# Transconductance.net
KiCad netlist of a schematic drawn in Altium Designer
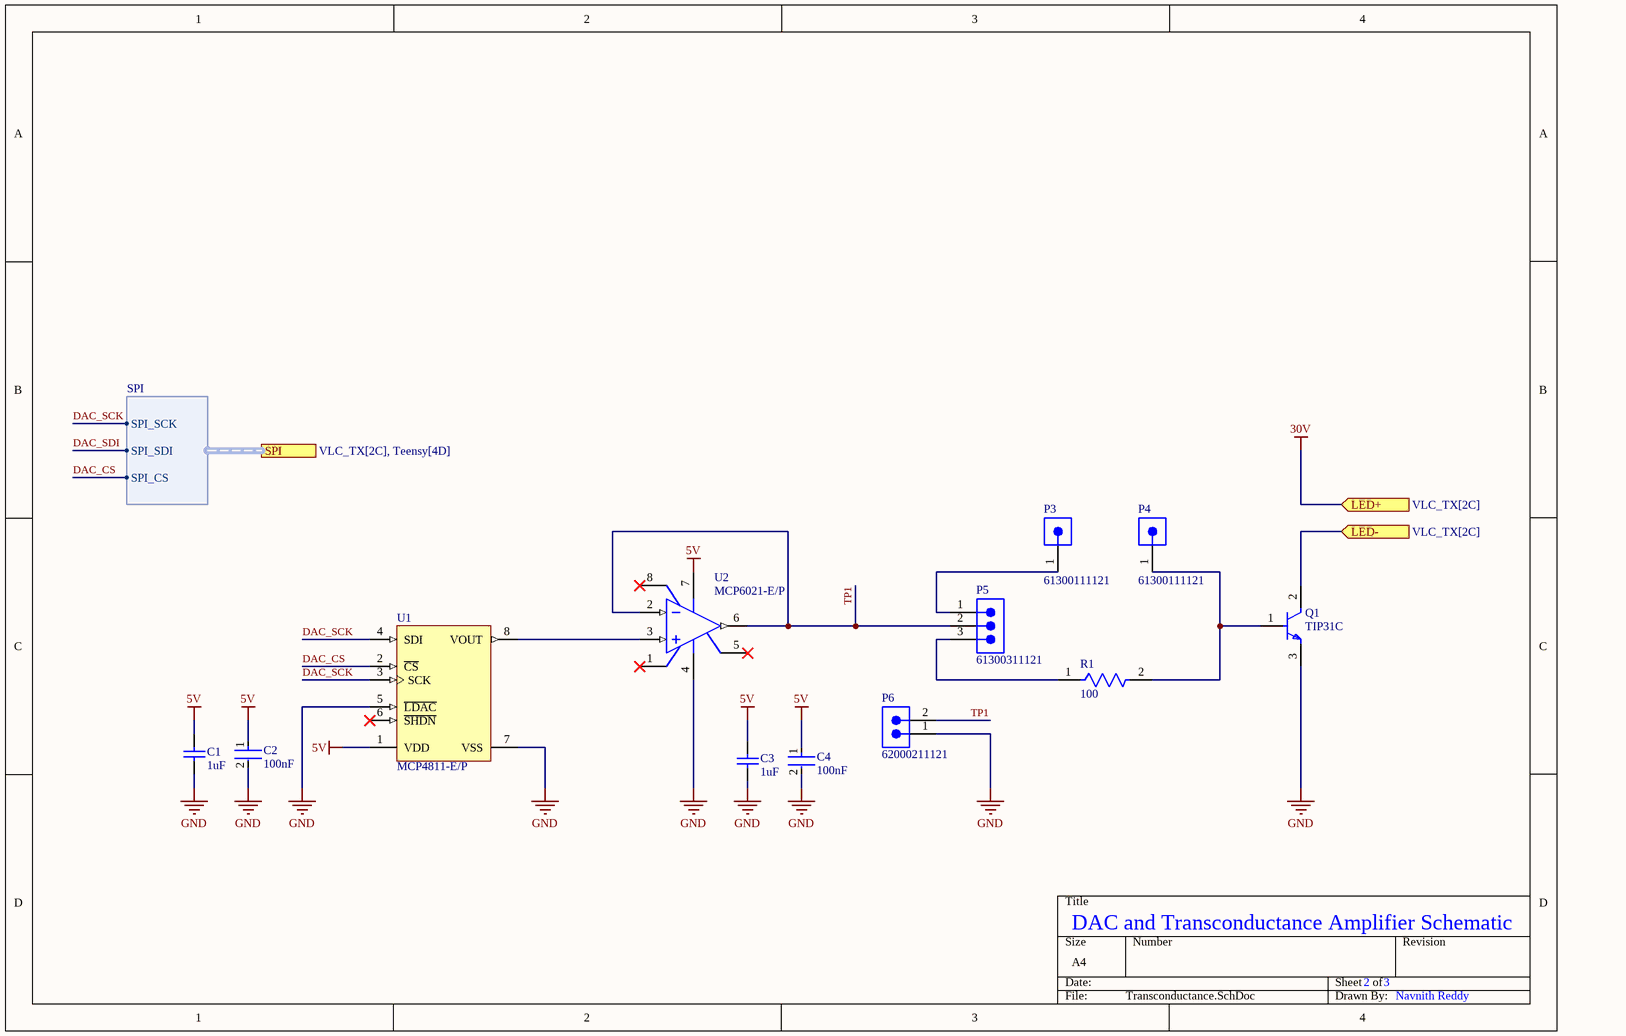
[diagram p0: Transconductance.SchDoc]

(export (version "E")
  (design (tool "Eeschema 10.0.6"))
  (components
    (comp (ref "C1")
      (value "1uF")
      (footprint "CAPC2013X145X50LL20T25")
      (fields (field (name "MANUFACTURER") "Kemet") (field (name "PART NUMBER") "C0805C105K4PACTU"))
      (libsource (lib "Altium Content Vault") (part "CAP"))
    )
    (comp (ref "C2")
      (value "100nF")
      (footprint "FP-C0805C-DN-MFG")
      (description "CAP CER 0.1UF 16V X7R 0805")
      (fields
        (field (name "OCTOPART") "https://octopart.com/c0805c104k4ractu-kemet-92155")
        (field (name "TOLERANCE") "0.1")
      )
      (libsource (lib "Altium Content Vault") (part "b4654b650e69147ec39a6b967a45e02"))
    )
    (comp (ref "C3")
      (value "1uF")
      (footprint "CAPC2013X145X50LL20T25")
      (fields (field (name "MANUFACTURER") "Kemet") (field (name "PART NUMBER") "C0805C105K4PACTU"))
      (libsource (lib "Altium Content Vault") (part "CAP"))
    )
    (comp (ref "C4")
      (value "100nF")
      (footprint "FP-C0805C-DN-MFG")
      (description "CAP CER 0.1UF 16V X7R 0805")
      (fields
        (field (name "OCTOPART") "https://octopart.com/c0805c104k4ractu-kemet-92155")
        (field (name "TOLERANCE") "0.1")
      )
      (libsource (lib "Altium Content Vault") (part "b4654b650e69147ec39a6b967a45e02"))
    )
    (comp (ref "P3")
      (value "61300111121")
      (footprint "61300111121")
      (libsource (lib "Altium Content Vault") (part "Header_Male_1R_01P"))
    )
    (comp (ref "P4")
      (value "61300111121")
      (footprint "61300111121")
      (libsource (lib "Altium Content Vault") (part "Header_Male_1R_01P"))
    )
    (comp (ref "P5")
      (value "61300311121")
      (footprint "61300311121")
      (libsource (lib "Altium Content Vault") (part "Header_Male_1R_03P"))
    )
    (comp (ref "P6")
      (value "62000211121")
      (footprint "62000211121")
      (libsource (lib "Altium Content Vault") (part "Header_Male_1R_02P"))
    )
    (comp (ref "Q1")
      (value "TIP31C")
      (footprint "FP-TO-220-P0A0015988-MFG")
      (description "TRANS NPN 100V 3A TO-220")
      (fields
        (field (name "OCTOPART") "https://octopart.com/tip31c-stmicroelectronics-15555")
        (field (name "MANUFACTURER") "STMicroelectronics")
      )
      (libsource (lib "Altium Content Vault") (part "1c57d9dae74fe2702546667b0e849db"))
    )
    (comp (ref "R1")
      (value "100")
      (footprint "FP-TNPW0805-e3-MFG")
      (fields (field (name "TOLERANCE") "1%"))
      (libsource (lib "Altium Content Vault") (part "1029c3af85768c4190bb7ad29bc67b5"))
    )
    (comp (ref "U1")
      (value "MCP4811-E/P")
      (footprint "PDIP300-P8")
      (description "10-Bit DACs with Internal VREF and SPI Interface, 8-Pin PDIP, Extended Temperature")
      (libsource (lib "Altium Content Vault") (part "CON-DAC-MCP4821-8"))
    )
    (comp (ref "U2")
      (value "MCP6021-E/P")
      (footprint "PDIP300-P8")
      (description "None")
      (libsource (lib "Altium Content Vault") (part "AMP-OPA-MCP6021-IL8"))
    )
  )
  (nets
    (net (code "2") (name "/DAC_CS") (class "Default")
      (node (ref "U1") (pin "2") (pinfunction "~{CS}_2") (pintype "input"))
    )
    (net (code "3") (name "/DAC_SCK") (class "Default")
      (node (ref "U1") (pin "3") (pinfunction "SCK_3") (pintype "input"))
      (node (ref "U1") (pin "4") (pinfunction "SDI_4") (pintype "input"))
    )
    (net (code "5") (name "/LED-") (class "Default")
      (node (ref "Q1") (pin "2") (pinfunction "C_2") (pintype "passive"))
    )
    (net (code "6") (name "/TP1") (class "Default")
      (node (ref "P5") (pin "2") (pinfunction "2_2") (pintype "passive"))
      (node (ref "P6") (pin "2") (pinfunction "2_2") (pintype "passive"))
      (node (ref "U2") (pin "2") (pinfunction "VIN-_2") (pintype "input"))
      (node (ref "U2") (pin "6") (pinfunction "VOUT_6") (pintype "output"))
    )
    (net (code "8") (name "5V") (class "Default")
      (node (ref "C1") (pin "2") (pinfunction "2_2") (pintype "passive"))
      (node (ref "C2") (pin "1") (pinfunction "1_1") (pintype "passive"))
      (node (ref "C3") (pin "2") (pinfunction "2_2") (pintype "passive"))
      (node (ref "C4") (pin "1") (pinfunction "1_1") (pintype "passive"))
      (node (ref "U1") (pin "1") (pinfunction "VDD_1") (pintype "power_in"))
      (node (ref "U2") (pin "7") (pinfunction "VDD_7") (pintype "power_in"))
    )
    (net (code "10") (name "GND") (class "Default")
      (node (ref "C1") (pin "1") (pinfunction "1_1") (pintype "passive"))
      (node (ref "C2") (pin "2") (pinfunction "2_2") (pintype "passive"))
      (node (ref "C3") (pin "1") (pinfunction "1_1") (pintype "passive"))
      (node (ref "C4") (pin "2") (pinfunction "2_2") (pintype "passive"))
      (node (ref "P6") (pin "1") (pinfunction "1_1") (pintype "passive"))
      (node (ref "Q1") (pin "3") (pinfunction "E_3") (pintype "passive"))
      (node (ref "U1") (pin "5") (pinfunction "~{LDAC}_5") (pintype "input"))
      (node (ref "U1") (pin "7") (pinfunction "VSS_7") (pintype "power_in"))
      (node (ref "U2") (pin "4") (pinfunction "VSS_4") (pintype "power_in"))
    )
    (net (code "11") (name "Net-(P3-Pad1)") (class "Default")
      (node (ref "P3") (pin "1") (pinfunction "1_1") (pintype "passive"))
      (node (ref "P5") (pin "1") (pinfunction "1_1") (pintype "passive"))
    )
    (net (code "12") (name "Net-(P5-Pad3)") (class "Default")
      (node (ref "P5") (pin "3") (pinfunction "3_3") (pintype "passive"))
      (node (ref "R1") (pin "1") (pinfunction "1_1") (pintype "passive"))
    )
    (net (code "13") (name "Net-(Q1-B)") (class "Default")
      (node (ref "P4") (pin "1") (pinfunction "1_1") (pintype "passive"))
      (node (ref "Q1") (pin "1") (pinfunction "B_1") (pintype "passive"))
      (node (ref "R1") (pin "2") (pinfunction "2_2") (pintype "passive"))
    )
    (net (code "14") (name "Net-(U1-VOUT)") (class "Default")
      (node (ref "U1") (pin "8") (pinfunction "VOUT_8") (pintype "output"))
      (node (ref "U2") (pin "3") (pinfunction "VIN+_3") (pintype "input"))
    )
    (net (code "15") (name "unconnected-(U1-~{SHDN}-Pad6)") (class "Default")
      (node (ref "U1") (pin "6") (pinfunction "~{SHDN}_6") (pintype "input+no_connect"))
    )
    (net (code "16") (name "unconnected-(U2-NC-Pad1)") (class "Default")
      (node (ref "U2") (pin "1") (pinfunction "NC_1") (pintype "passive+no_connect"))
    )
    (net (code "17") (name "unconnected-(U2-NC-Pad8)") (class "Default")
      (node (ref "U2") (pin "8") (pinfunction "NC_8") (pintype "passive+no_connect"))
    )
    (net (code "18") (name "unconnected-(U2-VREF-Pad5)") (class "Default")
      (node (ref "U2") (pin "5") (pinfunction "VREF_5") (pintype "power_in+no_connect"))
    )
  )
)
